# LiFiShieldV2.net
KiCad netlist of a schematic drawn in EAGLE
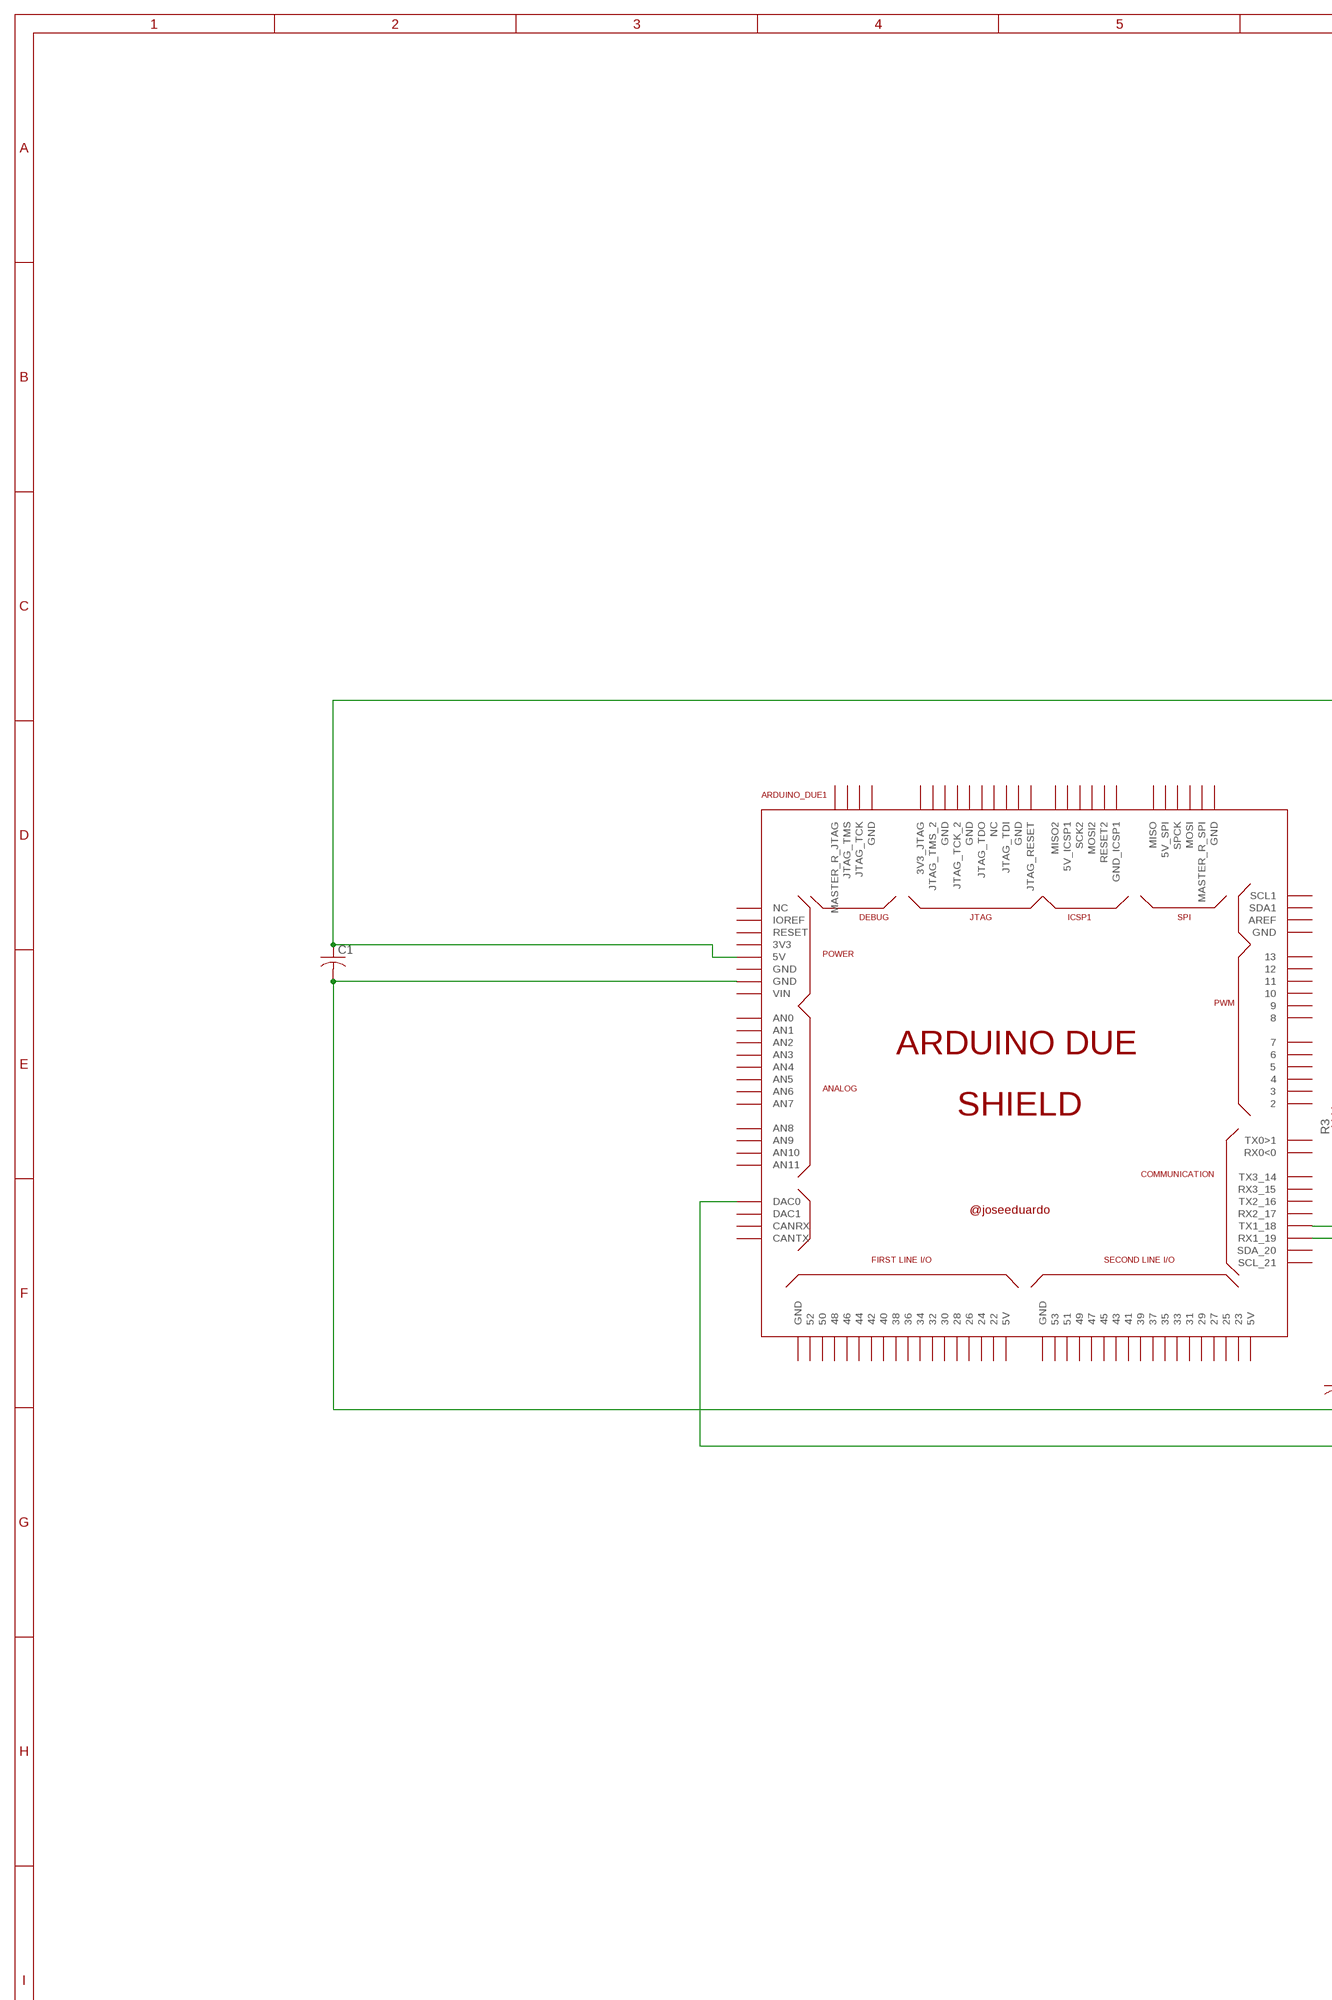
[diagram p0: schematic, sheet 1, part 1 of 2]
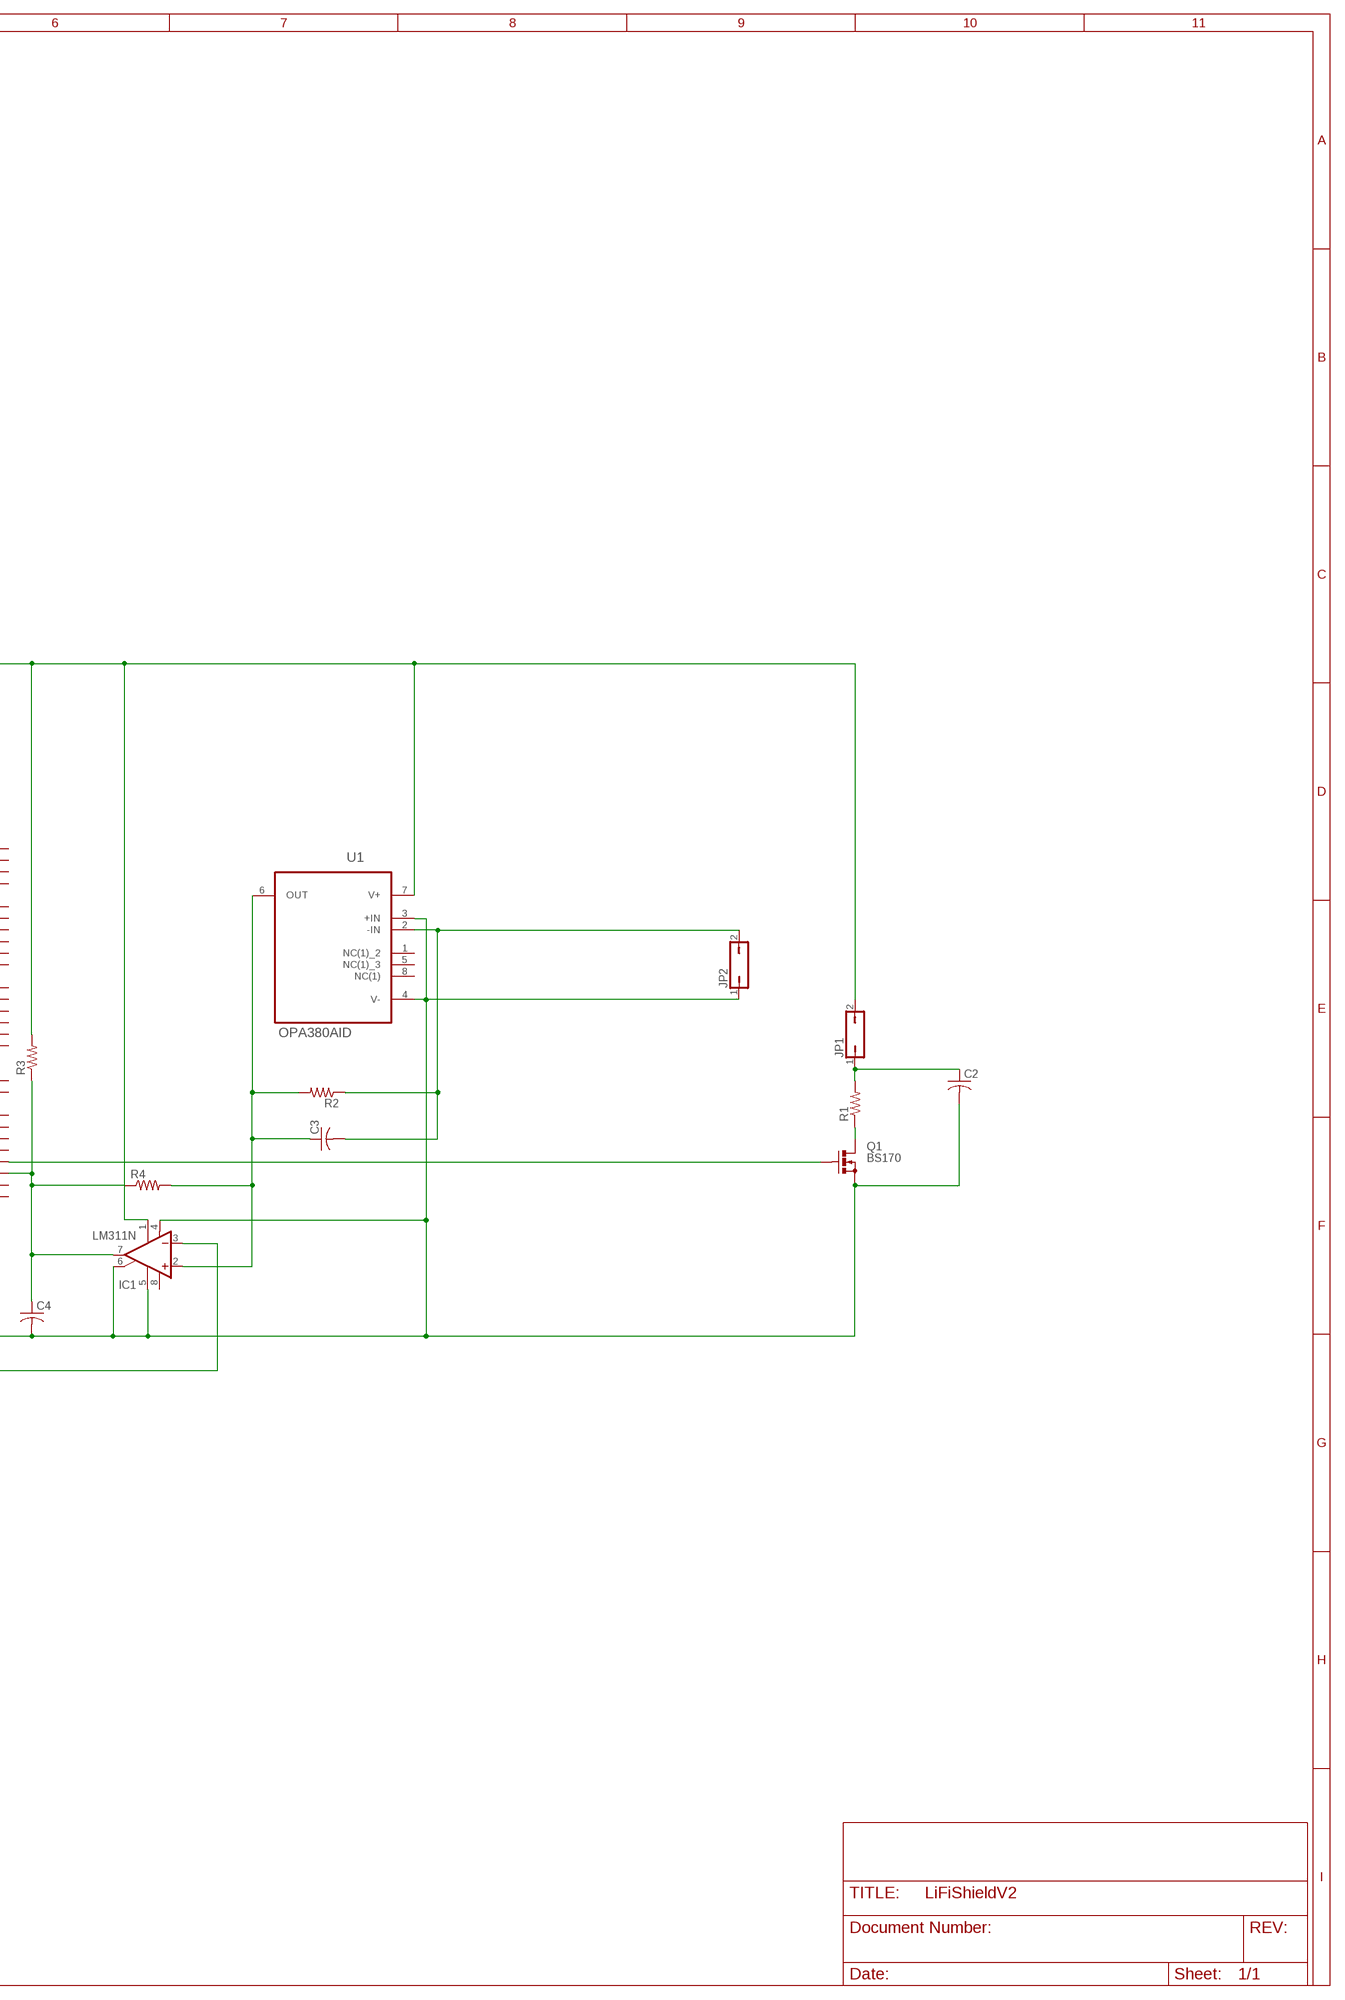
[diagram p1: schematic, sheet 1, part 2 of 2]

(export (version "E")
  (design (tool "Eeschema 10.0.6"))
  (components
    (comp (ref "ARDUINO_DUE1")
      (value "ARDUINO_DUE_SHIELD")
      (footprint "eagle-import:ARDUINO_DUE_SHIELD")
      (libsource (lib "eagle-import") (part "ARDUINO_DUE_SHIELD"))
    )
    (comp (ref "C1")
      (value "C-US050-055X075")
      (footprint "eagle-import:C050-055X075")
      (libsource (lib "eagle-import") (part "C-US050-055X075"))
    )
    (comp (ref "C2")
      (value "C-US050-055X075")
      (footprint "eagle-import:C050-055X075")
      (libsource (lib "eagle-import") (part "C-US050-055X075"))
    )
    (comp (ref "C3")
      (value "C-US050-055X075")
      (footprint "eagle-import:C050-055X075")
      (libsource (lib "eagle-import") (part "C-US050-055X075"))
    )
    (comp (ref "C4")
      (value "C-US050-055X075")
      (footprint "eagle-import:C050-055X075")
      (libsource (lib "eagle-import") (part "C-US050-055X075"))
    )
    (comp (ref "IC1")
      (value "LM311N")
      (footprint "eagle-import:DIL08")
      (libsource (lib "eagle-import") (part "LM311N"))
    )
    (comp (ref "JP1")
      (value "JP1Q")
      (footprint "eagle-import:JP1")
      (libsource (lib "eagle-import") (part "JP1Q"))
    )
    (comp (ref "JP2")
      (value "JP1Q")
      (footprint "eagle-import:JP1")
      (libsource (lib "eagle-import") (part "JP1Q"))
    )
    (comp (ref "Q1")
      (value "BS170")
      (footprint "eagle-import:SOT54E")
      (libsource (lib "eagle-import") (part "BS170"))
    )
    (comp (ref "R1")
      (value "R-US_0204/7")
      (footprint "eagle-import:0204_7")
      (libsource (lib "eagle-import") (part "R-US_0204/7"))
    )
    (comp (ref "R2")
      (value "R-US_0204/7")
      (footprint "eagle-import:0204_7")
      (libsource (lib "eagle-import") (part "R-US_0204/7"))
    )
    (comp (ref "R3")
      (value "R-US_0204/7")
      (footprint "eagle-import:0204_7")
      (libsource (lib "eagle-import") (part "R-US_0204/7"))
    )
    (comp (ref "R4")
      (value "R-US_0204/7")
      (footprint "eagle-import:0204_7")
      (libsource (lib "eagle-import") (part "R-US_0204/7"))
    )
    (comp (ref "U1")
      (value "OPA380AID")
      (footprint "eagle-import:SOIC127P600X175-8N")
      (libsource (lib "eagle-import") (part "OPA380AID"))
    )
  )
  (nets
    (net (code "1") (name "/V+") (class "Default")
      (node (ref "IC1") (pin "8") (pinfunction "V+_8") (pintype "power_in"))
    )
    (net (code "2") (name "Net-(ARDUINO_DUE1-RX1_19)") (class "Default")
      (node (ref "ARDUINO_DUE1") (pin "19") (pinfunction "RX1_19_19") (pintype "bidirectional"))
      (node (ref "C4") (pin "1") (pinfunction "1_1") (pintype "passive"))
      (node (ref "IC1") (pin "7") (pinfunction "OUT_7") (pintype "output"))
      (node (ref "R3") (pin "1") (pinfunction "1_1") (pintype "passive"))
      (node (ref "R4") (pin "1") (pinfunction "1_1") (pintype "passive"))
    )
    (net (code "3") (name "Net-(ARDUINO_DUE1-TX1_18)") (class "Default")
      (node (ref "ARDUINO_DUE1") (pin "18") (pinfunction "TX1_18_18") (pintype "bidirectional"))
      (node (ref "Q1") (pin "G") (pinfunction "G_G") (pintype "passive"))
    )
    (net (code "4") (name "Net-(C2-Pad1)") (class "Default")
      (node (ref "C2") (pin "1") (pinfunction "1_1") (pintype "passive"))
      (node (ref "JP1") (pin "1") (pinfunction "1_1") (pintype "passive"))
      (node (ref "R1") (pin "2") (pinfunction "2_2") (pintype "passive"))
    )
    (net (code "5") (name "Net-(IC1-+IN)") (class "Default")
      (node (ref "C3") (pin "1") (pinfunction "1_1") (pintype "passive"))
      (node (ref "IC1") (pin "2") (pinfunction "+IN_2") (pintype "input"))
      (node (ref "R2") (pin "2") (pinfunction "2_2") (pintype "passive"))
      (node (ref "R4") (pin "2") (pinfunction "2_2") (pintype "passive"))
      (node (ref "U1") (pin "6") (pinfunction "OUT_6") (pintype "output"))
    )
    (net (code "6") (name "Net-(IC1--IN)") (class "Default")
      (node (ref "ARDUINO_DUE1") (pin "DAC0") (pinfunction "DAC0_DAC0") (pintype "bidirectional"))
      (node (ref "IC1") (pin "3") (pinfunction "-IN_3") (pintype "input"))
    )
    (net (code "7") (name "Net-(IC1-GND)") (class "Default")
      (node (ref "ARDUINO_DUE1") (pin "5V0") (pinfunction "5V_5V0") (pintype "bidirectional"))
      (node (ref "C1") (pin "1") (pinfunction "1_1") (pintype "passive"))
      (node (ref "IC1") (pin "1") (pinfunction "GND_1") (pintype "passive"))
      (node (ref "JP1") (pin "2") (pinfunction "2_2") (pintype "passive"))
      (node (ref "R3") (pin "2") (pinfunction "2_2") (pintype "passive"))
      (node (ref "U1") (pin "7") (pinfunction "V+_7") (pintype "power_in"))
    )
    (net (code "8") (name "Net-(IC1-ON)") (class "Default")
      (node (ref "ARDUINO_DUE1") (pin "GND_1") (pinfunction "GND_GND_1") (pintype "bidirectional"))
      (node (ref "C1") (pin "2") (pinfunction "2_2") (pintype "passive"))
      (node (ref "C2") (pin "2") (pinfunction "2_2") (pintype "passive"))
      (node (ref "C4") (pin "2") (pinfunction "2_2") (pintype "passive"))
      (node (ref "IC1") (pin "4") (pinfunction "V-_4") (pintype "power_in"))
      (node (ref "IC1") (pin "5") (pinfunction "ON_5") (pintype "passive"))
      (node (ref "IC1") (pin "6") (pinfunction "ON/STR_6") (pintype "passive"))
      (node (ref "JP2") (pin "1") (pinfunction "1_1") (pintype "passive"))
      (node (ref "Q1") (pin "S") (pinfunction "S_S") (pintype "passive"))
      (node (ref "U1") (pin "3") (pinfunction "+IN_3") (pintype "input"))
      (node (ref "U1") (pin "4") (pinfunction "V-_4") (pintype "power_in"))
    )
    (net (code "9") (name "Net-(Q1-PadD)") (class "Default")
      (node (ref "Q1") (pin "D") (pinfunction "D_D") (pintype "passive"))
      (node (ref "R1") (pin "1") (pinfunction "1_1") (pintype "passive"))
    )
    (net (code "10") (name "Net-(U1--IN)") (class "Default")
      (node (ref "C3") (pin "2") (pinfunction "2_2") (pintype "passive"))
      (node (ref "JP2") (pin "2") (pinfunction "2_2") (pintype "passive"))
      (node (ref "R2") (pin "1") (pinfunction "1_1") (pintype "passive"))
      (node (ref "U1") (pin "2") (pinfunction "-IN_2") (pintype "input"))
    )
    (net (code "11") (name "unconnected-(ARDUINO_DUE1-5V-Pad5V0_1)") (class "Default")
      (node (ref "ARDUINO_DUE1") (pin "5V0_1") (pinfunction "5V_5V0_1") (pintype "bidirectional"))
    )
    (net (code "12") (name "unconnected-(ARDUINO_DUE1-5V-Pad5V0_2)") (class "Default")
      (node (ref "ARDUINO_DUE1") (pin "5V0_2") (pinfunction "5V_5V0_2") (pintype "bidirectional"))
    )
    (net (code "13") (name "unconnected-(ARDUINO_DUE1-5V_SPI-Pad5V_2)") (class "Default")
      (node (ref "ARDUINO_DUE1") (pin "5V_2") (pinfunction "5V_SPI_5V_2") (pintype "bidirectional"))
    )
    (net (code "14") (name "unconnected-(ARDUINO_DUE1-AN0-PadA0)") (class "Default")
      (node (ref "ARDUINO_DUE1") (pin "A0") (pinfunction "AN0_A0") (pintype "bidirectional"))
    )
    (net (code "15") (name "unconnected-(ARDUINO_DUE1-AN1-PadA1)") (class "Default")
      (node (ref "ARDUINO_DUE1") (pin "A1") (pinfunction "AN1_A1") (pintype "bidirectional"))
    )
    (net (code "16") (name "unconnected-(ARDUINO_DUE1-AN2-PadA2)") (class "Default")
      (node (ref "ARDUINO_DUE1") (pin "A2") (pinfunction "AN2_A2") (pintype "bidirectional"))
    )
    (net (code "17") (name "unconnected-(ARDUINO_DUE1-AN3-PadA3)") (class "Default")
      (node (ref "ARDUINO_DUE1") (pin "A3") (pinfunction "AN3_A3") (pintype "bidirectional"))
    )
    (net (code "18") (name "unconnected-(ARDUINO_DUE1-AN4-PadA4)") (class "Default")
      (node (ref "ARDUINO_DUE1") (pin "A4") (pinfunction "AN4_A4") (pintype "bidirectional"))
    )
    (net (code "19") (name "unconnected-(ARDUINO_DUE1-AN5-PadA5)") (class "Default")
      (node (ref "ARDUINO_DUE1") (pin "A5") (pinfunction "AN5_A5") (pintype "bidirectional"))
    )
    (net (code "20") (name "unconnected-(ARDUINO_DUE1-AN6-PadA6)") (class "Default")
      (node (ref "ARDUINO_DUE1") (pin "A6") (pinfunction "AN6_A6") (pintype "bidirectional"))
    )
    (net (code "21") (name "unconnected-(ARDUINO_DUE1-AN7-PadA7)") (class "Default")
      (node (ref "ARDUINO_DUE1") (pin "A7") (pinfunction "AN7_A7") (pintype "bidirectional"))
    )
    (net (code "22") (name "unconnected-(ARDUINO_DUE1-AN8-PadA8)") (class "Default")
      (node (ref "ARDUINO_DUE1") (pin "A8") (pinfunction "AN8_A8") (pintype "bidirectional"))
    )
    (net (code "23") (name "unconnected-(ARDUINO_DUE1-AN9-PadA9)") (class "Default")
      (node (ref "ARDUINO_DUE1") (pin "A9") (pinfunction "AN9_A9") (pintype "bidirectional"))
    )
    (net (code "24") (name "unconnected-(ARDUINO_DUE1-AN10-PadA10)") (class "Default")
      (node (ref "ARDUINO_DUE1") (pin "A10") (pinfunction "AN10_A10") (pintype "bidirectional"))
    )
    (net (code "25") (name "unconnected-(ARDUINO_DUE1-AN11-PadA11)") (class "Default")
      (node (ref "ARDUINO_DUE1") (pin "A11") (pinfunction "AN11_A11") (pintype "bidirectional"))
    )
    (net (code "26") (name "unconnected-(ARDUINO_DUE1-GND-PadGND_2)") (class "Default")
      (node (ref "ARDUINO_DUE1") (pin "GND_2") (pinfunction "GND_GND_2") (pintype "bidirectional"))
    )
    (net (code "27") (name "unconnected-(ARDUINO_DUE1-GND-PadGND_3)") (class "Default")
      (node (ref "ARDUINO_DUE1") (pin "GND_3") (pinfunction "GND_GND_3") (pintype "bidirectional"))
    )
    (net (code "28") (name "unconnected-(ARDUINO_DUE1-GND-PadGND_4)") (class "Default")
      (node (ref "ARDUINO_DUE1") (pin "GND_4") (pinfunction "GND_GND_4") (pintype "bidirectional"))
    )
    (net (code "29") (name "unconnected-(ARDUINO_DUE1-GND-PadGND_5)") (class "Default")
      (node (ref "ARDUINO_DUE1") (pin "GND_5") (pinfunction "GND_GND_5") (pintype "bidirectional"))
    )
    (net (code "30") (name "unconnected-(ARDUINO_DUE1-GND-PadGND_7)") (class "Default")
      (node (ref "ARDUINO_DUE1") (pin "GND_7") (pinfunction "GND_GND_7") (pintype "bidirectional"))
    )
    (net (code "31") (name "unconnected-(ARDUINO_DUE1-GND-PadGND_8)") (class "Default")
      (node (ref "ARDUINO_DUE1") (pin "GND_8") (pinfunction "GND_GND_8") (pintype "bidirectional"))
    )
    (net (code "32") (name "unconnected-(ARDUINO_DUE1-GND-PadGND_9)") (class "Default")
      (node (ref "ARDUINO_DUE1") (pin "GND_9") (pinfunction "GND_GND_9") (pintype "bidirectional"))
    )
    (net (code "33") (name "unconnected-(ARDUINO_DUE1-GND-PadGND_10)") (class "Default")
      (node (ref "ARDUINO_DUE1") (pin "GND_10") (pinfunction "GND_GND_10") (pintype "bidirectional"))
    )
    (net (code "34") (name "unconnected-(ARDUINO_DUE1-MASTER_R_JTAG-PadMASTER_RESET_JTAG)") (class "Default")
      (node (ref "ARDUINO_DUE1") (pin "MASTER_RESET_JTAG") (pinfunction "MASTER_R_JTAG_MASTER_RESET_JTAG") (pintype "bidirectional"))
    )
    (net (code "35") (name "unconnected-(ARDUINO_DUE1-MASTER_R_SPI-PadMASTER_RESET_SPI)") (class "Default")
      (node (ref "ARDUINO_DUE1") (pin "MASTER_RESET_SPI") (pinfunction "MASTER_R_SPI_MASTER_RESET_SPI") (pintype "bidirectional"))
    )
    (net (code "36") (name "unconnected-(ARDUINO_DUE1-NC-PadNC_2)") (class "Default")
      (node (ref "ARDUINO_DUE1") (pin "NC_2") (pinfunction "NC_NC_2") (pintype "no_connect"))
    )
    (net (code "37") (name "unconnected-(ARDUINO_DUE1-NC-PadNC_5)") (class "Default")
      (node (ref "ARDUINO_DUE1") (pin "NC_5") (pinfunction "NC_NC_5") (pintype "bidirectional"))
    )
    (net (code "38") (name "unconnected-(ARDUINO_DUE1-Pad2)") (class "Default")
      (node (ref "ARDUINO_DUE1") (pin "2") (pinfunction "2_2") (pintype "bidirectional"))
    )
    (net (code "39") (name "unconnected-(ARDUINO_DUE1-Pad3)") (class "Default")
      (node (ref "ARDUINO_DUE1") (pin "3") (pinfunction "3_3") (pintype "bidirectional"))
    )
    (net (code "40") (name "unconnected-(ARDUINO_DUE1-Pad3V3)") (class "Default")
      (node (ref "ARDUINO_DUE1") (pin "3V3") (pinfunction "3V3_3V3") (pintype "bidirectional"))
    )
    (net (code "41") (name "unconnected-(ARDUINO_DUE1-Pad3V3_JTAG)") (class "Default")
      (node (ref "ARDUINO_DUE1") (pin "3V3_JTAG") (pinfunction "3V3_JTAG_3V3_JTAG") (pintype "bidirectional"))
    )
    (net (code "42") (name "unconnected-(ARDUINO_DUE1-Pad4)") (class "Default")
      (node (ref "ARDUINO_DUE1") (pin "4") (pinfunction "4_4") (pintype "bidirectional"))
    )
    (net (code "43") (name "unconnected-(ARDUINO_DUE1-Pad5)") (class "Default")
      (node (ref "ARDUINO_DUE1") (pin "5") (pinfunction "5_5") (pintype "bidirectional"))
    )
    (net (code "44") (name "unconnected-(ARDUINO_DUE1-Pad5V_ICSP1)") (class "Default")
      (node (ref "ARDUINO_DUE1") (pin "5V_ICSP1") (pinfunction "5V_ICSP1_5V_ICSP1") (pintype "bidirectional"))
    )
    (net (code "45") (name "unconnected-(ARDUINO_DUE1-Pad6)") (class "Default")
      (node (ref "ARDUINO_DUE1") (pin "6") (pinfunction "6_6") (pintype "bidirectional"))
    )
    (net (code "46") (name "unconnected-(ARDUINO_DUE1-Pad7)") (class "Default")
      (node (ref "ARDUINO_DUE1") (pin "7") (pinfunction "7_7") (pintype "bidirectional"))
    )
    (net (code "47") (name "unconnected-(ARDUINO_DUE1-Pad8)") (class "Default")
      (node (ref "ARDUINO_DUE1") (pin "8") (pinfunction "8_8") (pintype "bidirectional"))
    )
    (net (code "48") (name "unconnected-(ARDUINO_DUE1-Pad9)") (class "Default")
      (node (ref "ARDUINO_DUE1") (pin "9") (pinfunction "9_9") (pintype "bidirectional"))
    )
    (net (code "49") (name "unconnected-(ARDUINO_DUE1-Pad10)") (class "Default")
      (node (ref "ARDUINO_DUE1") (pin "10") (pinfunction "10_10") (pintype "bidirectional"))
    )
    (net (code "50") (name "unconnected-(ARDUINO_DUE1-Pad11)") (class "Default")
      (node (ref "ARDUINO_DUE1") (pin "11") (pinfunction "11_11") (pintype "bidirectional"))
    )
    (net (code "51") (name "unconnected-(ARDUINO_DUE1-Pad12)") (class "Default")
      (node (ref "ARDUINO_DUE1") (pin "12") (pinfunction "12_12") (pintype "bidirectional"))
    )
    (net (code "52") (name "unconnected-(ARDUINO_DUE1-Pad13)") (class "Default")
      (node (ref "ARDUINO_DUE1") (pin "13") (pinfunction "13_13") (pintype "bidirectional"))
    )
    (net (code "53") (name "unconnected-(ARDUINO_DUE1-Pad22)") (class "Default")
      (node (ref "ARDUINO_DUE1") (pin "22") (pinfunction "22_22") (pintype "bidirectional"))
    )
    (net (code "54") (name "unconnected-(ARDUINO_DUE1-Pad23)") (class "Default")
      (node (ref "ARDUINO_DUE1") (pin "23") (pinfunction "23_23") (pintype "bidirectional"))
    )
    (net (code "55") (name "unconnected-(ARDUINO_DUE1-Pad24)") (class "Default")
      (node (ref "ARDUINO_DUE1") (pin "24") (pinfunction "24_24") (pintype "bidirectional"))
    )
    (net (code "56") (name "unconnected-(ARDUINO_DUE1-Pad25)") (class "Default")
      (node (ref "ARDUINO_DUE1") (pin "25") (pinfunction "25_25") (pintype "bidirectional"))
    )
    (net (code "57") (name "unconnected-(ARDUINO_DUE1-Pad26)") (class "Default")
      (node (ref "ARDUINO_DUE1") (pin "26") (pinfunction "26_26") (pintype "bidirectional"))
    )
    (net (code "58") (name "unconnected-(ARDUINO_DUE1-Pad27)") (class "Default")
      (node (ref "ARDUINO_DUE1") (pin "27") (pinfunction "27_27") (pintype "bidirectional"))
    )
    (net (code "59") (name "unconnected-(ARDUINO_DUE1-Pad28)") (class "Default")
      (node (ref "ARDUINO_DUE1") (pin "28") (pinfunction "28_28") (pintype "bidirectional"))
    )
    (net (code "60") (name "unconnected-(ARDUINO_DUE1-Pad29)") (class "Default")
      (node (ref "ARDUINO_DUE1") (pin "29") (pinfunction "29_29") (pintype "bidirectional"))
    )
    (net (code "61") (name "unconnected-(ARDUINO_DUE1-Pad30)") (class "Default")
      (node (ref "ARDUINO_DUE1") (pin "30") (pinfunction "30_30") (pintype "bidirectional"))
    )
    (net (code "62") (name "unconnected-(ARDUINO_DUE1-Pad31)") (class "Default")
      (node (ref "ARDUINO_DUE1") (pin "31") (pinfunction "31_31") (pintype "bidirectional"))
    )
    (net (code "63") (name "unconnected-(ARDUINO_DUE1-Pad32)") (class "Default")
      (node (ref "ARDUINO_DUE1") (pin "32") (pinfunction "32_32") (pintype "bidirectional"))
    )
    (net (code "64") (name "unconnected-(ARDUINO_DUE1-Pad33)") (class "Default")
      (node (ref "ARDUINO_DUE1") (pin "33") (pinfunction "33_33") (pintype "bidirectional"))
    )
    (net (code "65") (name "unconnected-(ARDUINO_DUE1-Pad34)") (class "Default")
      (node (ref "ARDUINO_DUE1") (pin "34") (pinfunction "34_34") (pintype "bidirectional"))
    )
    (net (code "66") (name "unconnected-(ARDUINO_DUE1-Pad35)") (class "Default")
      (node (ref "ARDUINO_DUE1") (pin "35") (pinfunction "35_35") (pintype "bidirectional"))
    )
    (net (code "67") (name "unconnected-(ARDUINO_DUE1-Pad36)") (class "Default")
      (node (ref "ARDUINO_DUE1") (pin "36") (pinfunction "36_36") (pintype "bidirectional"))
    )
    (net (code "68") (name "unconnected-(ARDUINO_DUE1-Pad37)") (class "Default")
      (node (ref "ARDUINO_DUE1") (pin "37") (pinfunction "37_37") (pintype "bidirectional"))
    )
    (net (code "69") (name "unconnected-(ARDUINO_DUE1-Pad38)") (class "Default")
      (node (ref "ARDUINO_DUE1") (pin "38") (pinfunction "38_38") (pintype "bidirectional"))
    )
    (net (code "70") (name "unconnected-(ARDUINO_DUE1-Pad39)") (class "Default")
      (node (ref "ARDUINO_DUE1") (pin "39") (pinfunction "39_39") (pintype "bidirectional"))
    )
    (net (code "71") (name "unconnected-(ARDUINO_DUE1-Pad40)") (class "Default")
      (node (ref "ARDUINO_DUE1") (pin "40") (pinfunction "40_40") (pintype "bidirectional"))
    )
    (net (code "72") (name "unconnected-(ARDUINO_DUE1-Pad41)") (class "Default")
      (node (ref "ARDUINO_DUE1") (pin "41") (pinfunction "41_41") (pintype "bidirectional"))
    )
    (net (code "73") (name "unconnected-(ARDUINO_DUE1-Pad42)") (class "Default")
      (node (ref "ARDUINO_DUE1") (pin "42") (pinfunction "42_42") (pintype "bidirectional"))
    )
    (net (code "74") (name "unconnected-(ARDUINO_DUE1-Pad43)") (class "Default")
      (node (ref "ARDUINO_DUE1") (pin "43") (pinfunction "43_43") (pintype "bidirectional"))
    )
    (net (code "75") (name "unconnected-(ARDUINO_DUE1-Pad44)") (class "Default")
      (node (ref "ARDUINO_DUE1") (pin "44") (pinfunction "44_44") (pintype "bidirectional"))
    )
    (net (code "76") (name "unconnected-(ARDUINO_DUE1-Pad45)") (class "Default")
      (node (ref "ARDUINO_DUE1") (pin "45") (pinfunction "45_45") (pintype "bidirectional"))
    )
    (net (code "77") (name "unconnected-(ARDUINO_DUE1-Pad46)") (class "Default")
      (node (ref "ARDUINO_DUE1") (pin "46") (pinfunction "46_46") (pintype "bidirectional"))
    )
    (net (code "78") (name "unconnected-(ARDUINO_DUE1-Pad47)") (class "Default")
      (node (ref "ARDUINO_DUE1") (pin "47") (pinfunction "47_47") (pintype "bidirectional"))
    )
    (net (code "79") (name "unconnected-(ARDUINO_DUE1-Pad48)") (class "Default")
      (node (ref "ARDUINO_DUE1") (pin "48") (pinfunction "48_48") (pintype "bidirectional"))
    )
    (net (code "80") (name "unconnected-(ARDUINO_DUE1-Pad49)") (class "Default")
      (node (ref "ARDUINO_DUE1") (pin "49") (pinfunction "49_49") (pintype "bidirectional"))
    )
    (net (code "81") (name "unconnected-(ARDUINO_DUE1-Pad50)") (class "Default")
      (node (ref "ARDUINO_DUE1") (pin "50") (pinfunction "50_50") (pintype "bidirectional"))
    )
    (net (code "82") (name "unconnected-(ARDUINO_DUE1-Pad51)") (class "Default")
      (node (ref "ARDUINO_DUE1") (pin "51") (pinfunction "51_51") (pintype "bidirectional"))
    )
    (net (code "83") (name "unconnected-(ARDUINO_DUE1-Pad52)") (class "Default")
      (node (ref "ARDUINO_DUE1") (pin "52") (pinfunction "52_52") (pintype "bidirectional"))
    )
    (net (code "84") (name "unconnected-(ARDUINO_DUE1-Pad53)") (class "Default")
      (node (ref "ARDUINO_DUE1") (pin "53") (pinfunction "53_53") (pintype "bidirectional"))
    )
    (net (code "85") (name "unconnected-(ARDUINO_DUE1-PadAREF)") (class "Default")
      (node (ref "ARDUINO_DUE1") (pin "AREF") (pinfunction "AREF_AREF") (pintype "bidirectional"))
    )
    (net (code "86") (name "unconnected-(ARDUINO_DUE1-PadCANRX)") (class "Default")
      (node (ref "ARDUINO_DUE1") (pin "CANRX") (pinfunction "CANRX_CANRX") (pintype "bidirectional"))
    )
    (net (code "87") (name "unconnected-(ARDUINO_DUE1-PadCANTX)") (class "Default")
      (node (ref "ARDUINO_DUE1") (pin "CANTX") (pinfunction "CANTX_CANTX") (pintype "bidirectional"))
    )
    (net (code "88") (name "unconnected-(ARDUINO_DUE1-PadDAC1)") (class "Default")
      (node (ref "ARDUINO_DUE1") (pin "DAC1") (pinfunction "DAC1_DAC1") (pintype "bidirectional"))
    )
    (net (code "89") (name "unconnected-(ARDUINO_DUE1-PadGND)") (class "Default")
      (node (ref "ARDUINO_DUE1") (pin "GND") (pinfunction "GND_GND") (pintype "bidirectional"))
    )
    (net (code "90") (name "unconnected-(ARDUINO_DUE1-PadGND_ICSP1)") (class "Default")
      (node (ref "ARDUINO_DUE1") (pin "GND_ICSP1") (pinfunction "GND_ICSP1_GND_ICSP1") (pintype "bidirectional"))
    )
    (net (code "91") (name "unconnected-(ARDUINO_DUE1-PadIOREF)") (class "Default")
      (node (ref "ARDUINO_DUE1") (pin "IOREF") (pinfunction "IOREF_IOREF") (pintype "bidirectional"))
    )
    (net (code "92") (name "unconnected-(ARDUINO_DUE1-PadJTAG_RESET)") (class "Default")
      (node (ref "ARDUINO_DUE1") (pin "JTAG_RESET") (pinfunction "JTAG_RESET_JTAG_RESET") (pintype "bidirectional"))
    )
    (net (code "93") (name "unconnected-(ARDUINO_DUE1-PadJTAG_TCK)") (class "Default")
      (node (ref "ARDUINO_DUE1") (pin "JTAG_TCK") (pinfunction "JTAG_TCK_JTAG_TCK") (pintype "bidirectional"))
    )
    (net (code "94") (name "unconnected-(ARDUINO_DUE1-PadJTAG_TCK_2)") (class "Default")
      (node (ref "ARDUINO_DUE1") (pin "JTAG_TCK_2") (pinfunction "JTAG_TCK_2_JTAG_TCK_2") (pintype "bidirectional"))
    )
    (net (code "95") (name "unconnected-(ARDUINO_DUE1-PadJTAG_TDI)") (class "Default")
      (node (ref "ARDUINO_DUE1") (pin "JTAG_TDI") (pinfunction "JTAG_TDI_JTAG_TDI") (pintype "bidirectional"))
    )
    (net (code "96") (name "unconnected-(ARDUINO_DUE1-PadJTAG_TDO)") (class "Default")
      (node (ref "ARDUINO_DUE1") (pin "JTAG_TDO") (pinfunction "JTAG_TDO_JTAG_TDO") (pintype "bidirectional"))
    )
    (net (code "97") (name "unconnected-(ARDUINO_DUE1-PadJTAG_TMS)") (class "Default")
      (node (ref "ARDUINO_DUE1") (pin "JTAG_TMS") (pinfunction "JTAG_TMS_JTAG_TMS") (pintype "bidirectional"))
    )
    (net (code "98") (name "unconnected-(ARDUINO_DUE1-PadJTAG_TMS_2)") (class "Default")
      (node (ref "ARDUINO_DUE1") (pin "JTAG_TMS_2") (pinfunction "JTAG_TMS_2_JTAG_TMS_2") (pintype "bidirectional"))
    )
    (net (code "99") (name "unconnected-(ARDUINO_DUE1-PadMISO)") (class "Default")
      (node (ref "ARDUINO_DUE1") (pin "MISO") (pinfunction "MISO_MISO") (pintype "bidirectional"))
    )
    (net (code "100") (name "unconnected-(ARDUINO_DUE1-PadMISO2)") (class "Default")
      (node (ref "ARDUINO_DUE1") (pin "MISO2") (pinfunction "MISO2_MISO2") (pintype "bidirectional"))
    )
    (net (code "101") (name "unconnected-(ARDUINO_DUE1-PadMOSI)") (class "Default")
      (node (ref "ARDUINO_DUE1") (pin "MOSI") (pinfunction "MOSI_MOSI") (pintype "bidirectional"))
    )
    (net (code "102") (name "unconnected-(ARDUINO_DUE1-PadMOSI2)") (class "Default")
      (node (ref "ARDUINO_DUE1") (pin "MOSI2") (pinfunction "MOSI2_MOSI2") (pintype "bidirectional"))
    )
    (net (code "103") (name "unconnected-(ARDUINO_DUE1-PadRESET)") (class "Default")
      (node (ref "ARDUINO_DUE1") (pin "RESET") (pinfunction "RESET_RESET") (pintype "bidirectional"))
    )
    (net (code "104") (name "unconnected-(ARDUINO_DUE1-PadRESET2)") (class "Default")
      (node (ref "ARDUINO_DUE1") (pin "RESET2") (pinfunction "RESET2_RESET2") (pintype "bidirectional"))
    )
    (net (code "105") (name "unconnected-(ARDUINO_DUE1-PadSCK2)") (class "Default")
      (node (ref "ARDUINO_DUE1") (pin "SCK2") (pinfunction "SCK2_SCK2") (pintype "bidirectional"))
    )
    (net (code "106") (name "unconnected-(ARDUINO_DUE1-PadSCL1)") (class "Default")
      (node (ref "ARDUINO_DUE1") (pin "SCL1") (pinfunction "SCL1_SCL1") (pintype "bidirectional"))
    )
    (net (code "107") (name "unconnected-(ARDUINO_DUE1-PadSDA1)") (class "Default")
      (node (ref "ARDUINO_DUE1") (pin "SDA1") (pinfunction "SDA1_SDA1") (pintype "bidirectional"))
    )
    (net (code "108") (name "unconnected-(ARDUINO_DUE1-PadSPCK)") (class "Default")
      (node (ref "ARDUINO_DUE1") (pin "SPCK") (pinfunction "SPCK_SPCK") (pintype "bidirectional"))
    )
    (net (code "109") (name "unconnected-(ARDUINO_DUE1-PadVIN)") (class "Default")
      (node (ref "ARDUINO_DUE1") (pin "VIN") (pinfunction "VIN_VIN") (pintype "bidirectional"))
    )
    (net (code "110") (name "unconnected-(ARDUINO_DUE1-RX0<0-Pad0)") (class "Default")
      (node (ref "ARDUINO_DUE1") (pin "0") (pinfunction "RX0<0_0") (pintype "bidirectional"))
    )
    (net (code "111") (name "unconnected-(ARDUINO_DUE1-RX2_17-Pad17)") (class "Default")
      (node (ref "ARDUINO_DUE1") (pin "17") (pinfunction "RX2_17_17") (pintype "bidirectional"))
    )
    (net (code "112") (name "unconnected-(ARDUINO_DUE1-RX3_15-Pad15)") (class "Default")
      (node (ref "ARDUINO_DUE1") (pin "15") (pinfunction "RX3_15_15") (pintype "bidirectional"))
    )
    (net (code "113") (name "unconnected-(ARDUINO_DUE1-SCL_21-Pad21)") (class "Default")
      (node (ref "ARDUINO_DUE1") (pin "21") (pinfunction "SCL_21_21") (pintype "bidirectional"))
    )
    (net (code "114") (name "unconnected-(ARDUINO_DUE1-SDA_20-Pad20)") (class "Default")
      (node (ref "ARDUINO_DUE1") (pin "20") (pinfunction "SDA_20_20") (pintype "bidirectional"))
    )
    (net (code "115") (name "unconnected-(ARDUINO_DUE1-TX0>1-Pad1)") (class "Default")
      (node (ref "ARDUINO_DUE1") (pin "1") (pinfunction "TX0>1_1") (pintype "bidirectional"))
    )
    (net (code "116") (name "unconnected-(ARDUINO_DUE1-TX2_16-Pad16)") (class "Default")
      (node (ref "ARDUINO_DUE1") (pin "16") (pinfunction "TX2_16_16") (pintype "bidirectional"))
    )
    (net (code "117") (name "unconnected-(ARDUINO_DUE1-TX3_14-Pad14)") (class "Default")
      (node (ref "ARDUINO_DUE1") (pin "14") (pinfunction "TX3_14_14") (pintype "bidirectional"))
    )
    (net (code "118") (name "unconnected-(U1-NC(1)-Pad8)") (class "Default")
      (node (ref "U1") (pin "8") (pinfunction "NC(1)_8") (pintype "no_connect"))
    )
    (net (code "119") (name "unconnected-(U1-NC(1)_2-Pad1)") (class "Default")
      (node (ref "U1") (pin "1") (pinfunction "NC(1)_2_1") (pintype "no_connect"))
    )
    (net (code "120") (name "unconnected-(U1-NC(1)_3-Pad5)") (class "Default")
      (node (ref "U1") (pin "5") (pinfunction "NC(1)_3_5") (pintype "no_connect"))
    )
  )
)
